# 06_SENSORS_old.net
KiCad netlist of a schematic drawn in Altium Designer
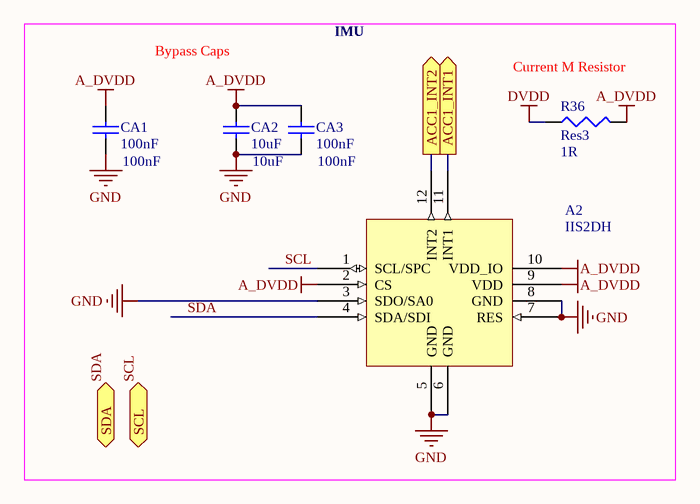
[diagram p0: 06_SENSORS_old.SchDoc]

(export (version "E")
  (design (tool "Eeschema 10.0.6"))
  (components
    (comp (ref "A2")
      (value "IIS2DH")
      (footprint "*LGA12R50P4X4_200X200X86")
      (libsource (lib "Schlib1") (part "IIS2DH"))
    )
    (comp (ref "CA1")
      (value "100nF")
      (footprint "0402")
      (description "Capacitor (Semiconductor SIM Model)")
      (fields (field (name "ALTIUM_VALUE") "100nF") (field (name "PUBLISHER") "Altium Limited"))
      (libsource (lib "Miscellaneous Devices") (part "Cap Semi"))
    )
    (comp (ref "CA2")
      (value "10uF")
      (footprint "0402")
      (description "Capacitor (Semiconductor SIM Model)")
      (fields (field (name "ALTIUM_VALUE") "10uF") (field (name "PUBLISHER") "Altium Limited"))
      (libsource (lib "Miscellaneous Devices") (part "Cap Semi"))
    )
    (comp (ref "CA3")
      (value "100nF")
      (footprint "0402")
      (description "Capacitor (Semiconductor SIM Model)")
      (fields (field (name "ALTIUM_VALUE") "100nF") (field (name "PUBLISHER") "Altium Limited"))
      (libsource (lib "Miscellaneous Devices") (part "Cap Semi"))
    )
    (comp (ref "R36")
      (value "Res3")
      (footprint "0402")
      (description "Resistor")
      (fields (field (name "ALTIUM_VALUE") "1R") (field (name "PUBLISHER") "Altium Limited"))
      (libsource (lib "Miscellaneous Devices") (part "Res3"))
    )
  )
  (nets
    (net (code "1") (name "/ACC1_INT1") (class "Default")
      (node (ref "A2") (pin "11") (pinfunction "INT1_11") (pintype "output"))
    )
    (net (code "2") (name "/ACC1_INT2") (class "Default")
      (node (ref "A2") (pin "12") (pinfunction "INT2_12") (pintype "output"))
    )
    (net (code "3") (name "/SCL") (class "Default")
      (node (ref "A2") (pin "1") (pinfunction "SCL/SPC_1") (pintype "bidirectional"))
    )
    (net (code "4") (name "/SDA") (class "Default")
      (node (ref "A2") (pin "4") (pinfunction "SDA/SDI_4") (pintype "input"))
    )
    (net (code "5") (name "A_DVDD") (class "Default")
      (node (ref "A2") (pin "10") (pinfunction "VDD_IO_10") (pintype "power_in"))
      (node (ref "A2") (pin "2") (pinfunction "CS_2") (pintype "input"))
      (node (ref "A2") (pin "9") (pinfunction "VDD_9") (pintype "power_in"))
      (node (ref "CA1") (pin "2") (pinfunction "2_2") (pintype "passive"))
      (node (ref "CA2") (pin "2") (pinfunction "2_2") (pintype "passive"))
      (node (ref "CA3") (pin "2") (pinfunction "2_2") (pintype "passive"))
      (node (ref "R36") (pin "2") (pinfunction "2_2") (pintype "passive"))
    )
    (net (code "6") (name "DVDD") (class "Default")
      (node (ref "R36") (pin "1") (pinfunction "1_1") (pintype "passive"))
    )
    (net (code "7") (name "GND") (class "Default")
      (node (ref "A2") (pin "3") (pinfunction "SDO/SA0_3") (pintype "input"))
      (node (ref "A2") (pin "5") (pinfunction "GND_5") (pintype "power_in"))
      (node (ref "A2") (pin "6") (pinfunction "GND_6") (pintype "power_in"))
      (node (ref "A2") (pin "7") (pinfunction "RES_7") (pintype "input"))
      (node (ref "A2") (pin "8") (pinfunction "GND_8") (pintype "power_in"))
      (node (ref "CA1") (pin "1") (pinfunction "1_1") (pintype "passive"))
      (node (ref "CA2") (pin "1") (pinfunction "1_1") (pintype "passive"))
      (node (ref "CA3") (pin "1") (pinfunction "1_1") (pintype "passive"))
    )
  )
)
